# BOARD_GPIO.net
KiCad netlist of a schematic drawn in Altium Designer
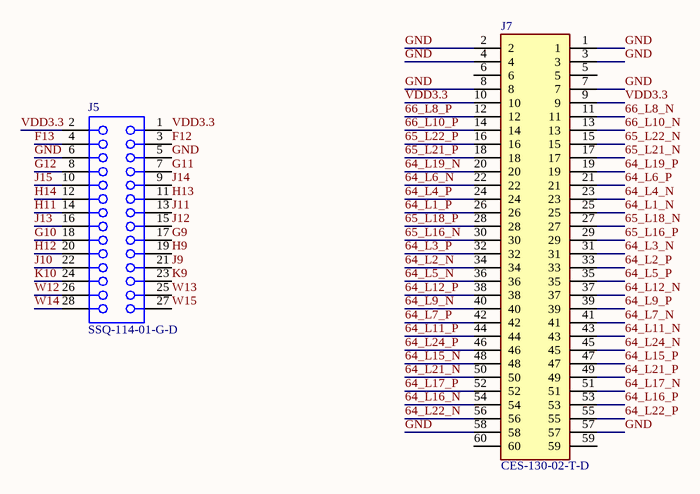
[diagram p0: BOARD_GPIO.SchDoc]

(export (version "E")
  (design (tool "Eeschema 10.0.6"))
  (components
    (comp (ref "J5")
      (value "SSQ-114-01-G-D")
      (footprint "SMTC-SSQ-114-01-X-D")
      (description "SQ Post Socket, Through-hole, Vertical, -55 to 125 degC, 2.54 mm Pitch, 28-Pin, Female, RoHS")
      (fields (field (name "MANUFACTURER") "Samtec"))
      (libsource (lib "Altium Content Vault") (part "SMTC-SSQ-114-01-X-D"))
    )
    (comp (ref "J7")
      (value "CES-130-02-T-D")
      (footprint "SamacSys:CES-130-XX-X-D")
      (description "Connector")
      (libsource (lib "*") (part "CES-130-02-T-D"))
    )
  )
  (nets
    (net (code "1") (name "/64_L1_N") (class "Default")
      (node (ref "J7") (pin "25") (pinfunction "25_25") (pintype "passive"))
    )
    (net (code "2") (name "/64_L1_P") (class "Default")
      (node (ref "J7") (pin "26") (pinfunction "26_26") (pintype "passive"))
    )
    (net (code "3") (name "/64_L2_N") (class "Default")
      (node (ref "J7") (pin "34") (pinfunction "34_34") (pintype "passive"))
    )
    (net (code "4") (name "/64_L2_P") (class "Default")
      (node (ref "J7") (pin "33") (pinfunction "33_33") (pintype "passive"))
    )
    (net (code "5") (name "/64_L3_N") (class "Default")
      (node (ref "J7") (pin "31") (pinfunction "31_31") (pintype "passive"))
    )
    (net (code "6") (name "/64_L3_P") (class "Default")
      (node (ref "J7") (pin "32") (pinfunction "32_32") (pintype "passive"))
    )
    (net (code "7") (name "/64_L4_N") (class "Default")
      (node (ref "J7") (pin "23") (pinfunction "23_23") (pintype "passive"))
    )
    (net (code "8") (name "/64_L4_P") (class "Default")
      (node (ref "J7") (pin "24") (pinfunction "24_24") (pintype "passive"))
    )
    (net (code "9") (name "/64_L5_N") (class "Default")
      (node (ref "J7") (pin "36") (pinfunction "36_36") (pintype "passive"))
    )
    (net (code "10") (name "/64_L5_P") (class "Default")
      (node (ref "J7") (pin "35") (pinfunction "35_35") (pintype "passive"))
    )
    (net (code "11") (name "/64_L6_N") (class "Default")
      (node (ref "J7") (pin "22") (pinfunction "22_22") (pintype "passive"))
    )
    (net (code "12") (name "/64_L6_P") (class "Default")
      (node (ref "J7") (pin "21") (pinfunction "21_21") (pintype "passive"))
    )
    (net (code "13") (name "/64_L7_N") (class "Default")
      (node (ref "J7") (pin "41") (pinfunction "41_41") (pintype "passive"))
    )
    (net (code "14") (name "/64_L7_P") (class "Default")
      (node (ref "J7") (pin "42") (pinfunction "42_42") (pintype "passive"))
    )
    (net (code "15") (name "/64_L9_N") (class "Default")
      (node (ref "J7") (pin "40") (pinfunction "40_40") (pintype "passive"))
    )
    (net (code "16") (name "/64_L9_P") (class "Default")
      (node (ref "J7") (pin "39") (pinfunction "39_39") (pintype "passive"))
    )
    (net (code "17") (name "/64_L11_N") (class "Default")
      (node (ref "J7") (pin "43") (pinfunction "43_43") (pintype "passive"))
    )
    (net (code "18") (name "/64_L11_P") (class "Default")
      (node (ref "J7") (pin "44") (pinfunction "44_44") (pintype "passive"))
    )
    (net (code "19") (name "/64_L12_N") (class "Default")
      (node (ref "J7") (pin "37") (pinfunction "37_37") (pintype "passive"))
    )
    (net (code "20") (name "/64_L12_P") (class "Default")
      (node (ref "J7") (pin "38") (pinfunction "38_38") (pintype "passive"))
    )
    (net (code "21") (name "/64_L15_N") (class "Default")
      (node (ref "J7") (pin "48") (pinfunction "48_48") (pintype "passive"))
    )
    (net (code "22") (name "/64_L15_P") (class "Default")
      (node (ref "J7") (pin "47") (pinfunction "47_47") (pintype "passive"))
    )
    (net (code "23") (name "/64_L16_N") (class "Default")
      (node (ref "J7") (pin "54") (pinfunction "54_54") (pintype "passive"))
    )
    (net (code "24") (name "/64_L16_P") (class "Default")
      (node (ref "J7") (pin "53") (pinfunction "53_53") (pintype "passive"))
    )
    (net (code "25") (name "/64_L17_N") (class "Default")
      (node (ref "J7") (pin "51") (pinfunction "51_51") (pintype "passive"))
    )
    (net (code "26") (name "/64_L17_P") (class "Default")
      (node (ref "J7") (pin "52") (pinfunction "52_52") (pintype "passive"))
    )
    (net (code "27") (name "/64_L19_N") (class "Default")
      (node (ref "J7") (pin "20") (pinfunction "20_20") (pintype "passive"))
    )
    (net (code "28") (name "/64_L19_P") (class "Default")
      (node (ref "J7") (pin "19") (pinfunction "19_19") (pintype "passive"))
    )
    (net (code "29") (name "/64_L21_N") (class "Default")
      (node (ref "J7") (pin "50") (pinfunction "50_50") (pintype "passive"))
    )
    (net (code "30") (name "/64_L21_P") (class "Default")
      (node (ref "J7") (pin "49") (pinfunction "49_49") (pintype "passive"))
    )
    (net (code "31") (name "/64_L22_N") (class "Default")
      (node (ref "J7") (pin "56") (pinfunction "56_56") (pintype "passive"))
    )
    (net (code "32") (name "/64_L22_P") (class "Default")
      (node (ref "J7") (pin "55") (pinfunction "55_55") (pintype "passive"))
    )
    (net (code "33") (name "/64_L24_N") (class "Default")
      (node (ref "J7") (pin "45") (pinfunction "45_45") (pintype "passive"))
    )
    (net (code "34") (name "/64_L24_P") (class "Default")
      (node (ref "J7") (pin "46") (pinfunction "46_46") (pintype "passive"))
    )
    (net (code "35") (name "/65_L16_N") (class "Default")
      (node (ref "J7") (pin "30") (pinfunction "30_30") (pintype "passive"))
    )
    (net (code "36") (name "/65_L16_P") (class "Default")
      (node (ref "J7") (pin "29") (pinfunction "29_29") (pintype "passive"))
    )
    (net (code "37") (name "/65_L18_N") (class "Default")
      (node (ref "J7") (pin "27") (pinfunction "27_27") (pintype "passive"))
    )
    (net (code "38") (name "/65_L18_P") (class "Default")
      (node (ref "J7") (pin "28") (pinfunction "28_28") (pintype "passive"))
    )
    (net (code "39") (name "/65_L21_N") (class "Default")
      (node (ref "J7") (pin "17") (pinfunction "17_17") (pintype "passive"))
    )
    (net (code "40") (name "/65_L21_P") (class "Default")
      (node (ref "J7") (pin "18") (pinfunction "18_18") (pintype "passive"))
    )
    (net (code "41") (name "/65_L22_N") (class "Default")
      (node (ref "J7") (pin "15") (pinfunction "15_15") (pintype "passive"))
    )
    (net (code "42") (name "/65_L22_P") (class "Default")
      (node (ref "J7") (pin "16") (pinfunction "16_16") (pintype "passive"))
    )
    (net (code "43") (name "/66_L8_N") (class "Default")
      (node (ref "J7") (pin "11") (pinfunction "11_11") (pintype "passive"))
    )
    (net (code "44") (name "/66_L8_P") (class "Default")
      (node (ref "J7") (pin "12") (pinfunction "12_12") (pintype "passive"))
    )
    (net (code "45") (name "/66_L10_N") (class "Default")
      (node (ref "J7") (pin "13") (pinfunction "13_13") (pintype "passive"))
    )
    (net (code "46") (name "/66_L10_P") (class "Default")
      (node (ref "J7") (pin "14") (pinfunction "14_14") (pintype "passive"))
    )
    (net (code "47") (name "/F12") (class "Default")
      (node (ref "J5") (pin "3") (pinfunction "3_3") (pintype "passive"))
    )
    (net (code "48") (name "/F13") (class "Default")
      (node (ref "J5") (pin "4") (pinfunction "4_4") (pintype "passive"))
    )
    (net (code "49") (name "/G9") (class "Default")
      (node (ref "J5") (pin "17") (pinfunction "17_17") (pintype "passive"))
    )
    (net (code "50") (name "/G10") (class "Default")
      (node (ref "J5") (pin "18") (pinfunction "18_18") (pintype "passive"))
    )
    (net (code "51") (name "/G11") (class "Default")
      (node (ref "J5") (pin "7") (pinfunction "7_7") (pintype "passive"))
    )
    (net (code "52") (name "/G12") (class "Default")
      (node (ref "J5") (pin "8") (pinfunction "8_8") (pintype "passive"))
    )
    (net (code "53") (name "/GND") (class "Default")
      (node (ref "J5") (pin "5") (pinfunction "5_5") (pintype "passive"))
      (node (ref "J5") (pin "6") (pinfunction "6_6") (pintype "passive"))
      (node (ref "J7") (pin "1") (pinfunction "1_1") (pintype "passive"))
      (node (ref "J7") (pin "2") (pinfunction "2_2") (pintype "passive"))
      (node (ref "J7") (pin "3") (pinfunction "3_3") (pintype "passive"))
      (node (ref "J7") (pin "4") (pinfunction "4_4") (pintype "passive"))
      (node (ref "J7") (pin "57") (pinfunction "57_57") (pintype "passive"))
      (node (ref "J7") (pin "58") (pinfunction "58_58") (pintype "passive"))
      (node (ref "J7") (pin "7") (pinfunction "7_7") (pintype "passive"))
      (node (ref "J7") (pin "8") (pinfunction "8_8") (pintype "passive"))
    )
    (net (code "54") (name "/H9") (class "Default")
      (node (ref "J5") (pin "19") (pinfunction "19_19") (pintype "passive"))
    )
    (net (code "55") (name "/H11") (class "Default")
      (node (ref "J5") (pin "14") (pinfunction "14_14") (pintype "passive"))
    )
    (net (code "56") (name "/H12") (class "Default")
      (node (ref "J5") (pin "20") (pinfunction "20_20") (pintype "passive"))
    )
    (net (code "57") (name "/H13") (class "Default")
      (node (ref "J5") (pin "11") (pinfunction "11_11") (pintype "passive"))
    )
    (net (code "58") (name "/H14") (class "Default")
      (node (ref "J5") (pin "12") (pinfunction "12_12") (pintype "passive"))
    )
    (net (code "59") (name "/J9") (class "Default")
      (node (ref "J5") (pin "21") (pinfunction "21_21") (pintype "passive"))
    )
    (net (code "60") (name "/J10") (class "Default")
      (node (ref "J5") (pin "22") (pinfunction "22_22") (pintype "passive"))
    )
    (net (code "61") (name "/J11") (class "Default")
      (node (ref "J5") (pin "13") (pinfunction "13_13") (pintype "passive"))
    )
    (net (code "62") (name "/J12") (class "Default")
      (node (ref "J5") (pin "15") (pinfunction "15_15") (pintype "passive"))
    )
    (net (code "63") (name "/J13") (class "Default")
      (node (ref "J5") (pin "16") (pinfunction "16_16") (pintype "passive"))
    )
    (net (code "64") (name "/J14") (class "Default")
      (node (ref "J5") (pin "9") (pinfunction "9_9") (pintype "passive"))
    )
    (net (code "65") (name "/J15") (class "Default")
      (node (ref "J5") (pin "10") (pinfunction "10_10") (pintype "passive"))
    )
    (net (code "66") (name "/K9") (class "Default")
      (node (ref "J5") (pin "23") (pinfunction "23_23") (pintype "passive"))
    )
    (net (code "67") (name "/K10") (class "Default")
      (node (ref "J5") (pin "24") (pinfunction "24_24") (pintype "passive"))
    )
    (net (code "68") (name "/VDD3.3") (class "Default")
      (node (ref "J5") (pin "1") (pinfunction "1_1") (pintype "passive"))
      (node (ref "J5") (pin "2") (pinfunction "2_2") (pintype "passive"))
      (node (ref "J7") (pin "10") (pinfunction "10_10") (pintype "passive"))
      (node (ref "J7") (pin "9") (pinfunction "9_9") (pintype "passive"))
    )
    (net (code "69") (name "/W12") (class "Default")
      (node (ref "J5") (pin "26") (pinfunction "26_26") (pintype "passive"))
    )
    (net (code "70") (name "/W13") (class "Default")
      (node (ref "J5") (pin "25") (pinfunction "25_25") (pintype "passive"))
    )
    (net (code "71") (name "/W14") (class "Default")
      (node (ref "J5") (pin "28") (pinfunction "28_28") (pintype "passive"))
    )
    (net (code "72") (name "/W15") (class "Default")
      (node (ref "J5") (pin "27") (pinfunction "27_27") (pintype "passive"))
    )
    (net (code "73") (name "unconnected-(J7-Pad5)") (class "Default")
      (node (ref "J7") (pin "5") (pinfunction "5_5") (pintype "passive"))
    )
    (net (code "74") (name "unconnected-(J7-Pad6)") (class "Default")
      (node (ref "J7") (pin "6") (pinfunction "6_6") (pintype "passive"))
    )
    (net (code "75") (name "unconnected-(J7-Pad59)") (class "Default")
      (node (ref "J7") (pin "59") (pinfunction "59_59") (pintype "passive"))
    )
    (net (code "76") (name "unconnected-(J7-Pad60)") (class "Default")
      (node (ref "J7") (pin "60") (pinfunction "60_60") (pintype "passive"))
    )
  )
)
